# LDO_Regulator.net
KiCad netlist of a schematic drawn in Altium Designer
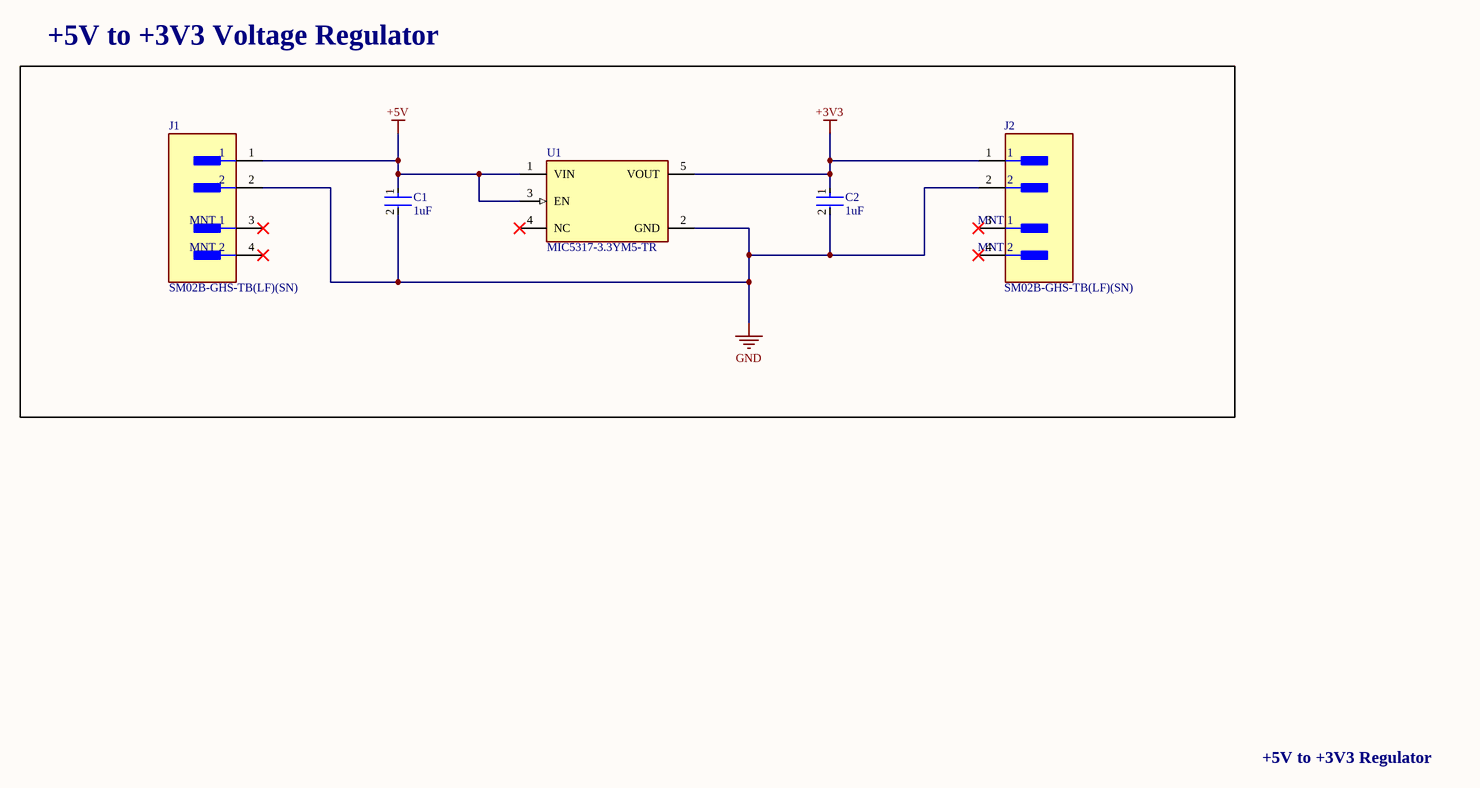
[diagram p0: LDO Regulator.SchDoc]

(export (version "E")
  (design (tool "Eeschema 10.0.6"))
  (components
    (comp (ref "C1")
      (value "1uF")
      (footprint "FP-CC0805-0_85-MFG")
      (description "CAP CER 1UF 10V X7R 0805")
      (fields
        (field (name "MANUFACTURER") "Yageo")
        (field (name "OCTOPART") "https://octopart.com/cc0805kkx7r6bb105-yageo-42522859")
      )
      (libsource (lib "Altium Content Vault") (part "11868f565c42a9108669ba33697ecf6"))
    )
    (comp (ref "C2")
      (value "1uF")
      (footprint "FP-CC0805-0_85-MFG")
      (description "CAP CER 1UF 10V X7R 0805")
      (fields
        (field (name "MANUFACTURER") "Yageo")
        (field (name "OCTOPART") "https://octopart.com/cc0805kkx7r6bb105-yageo-42522859")
      )
      (libsource (lib "Altium Content Vault") (part "11868f565c42a9108669ba33697ecf6"))
    )
    (comp (ref "J1")
      (value "SM02B-GHS-TB(LF)(SN)")
      (footprint "FP-SM02B-GHS-TB_LF_SN-MFG")
      (description "CONN HEADER SMD R/A 2POS 1.25MM")
      (libsource (lib "Altium Content Vault") (part "56ec3178a87b3978bdc1b3682cd516a"))
    )
    (comp (ref "J2")
      (value "SM02B-GHS-TB(LF)(SN)")
      (footprint "FP-SM02B-GHS-TB_LF_SN-MFG")
      (description "CONN HEADER SMD R/A 2POS 1.25MM")
      (libsource (lib "") (part "56ec3178a87b3978bdc1b3682cd516a_1"))
    )
    (comp (ref "U1")
      (value "MIC5317-3.3YM5-TR")
      (footprint "FP-SOT23-5LD-PL-1-MFG")
      (description "IC REG LINEAR 3.3V 150MA SOT23-5")
      (libsource (lib "Altium Content Vault") (part "0a093dae7315cdc977fd108dde87457"))
    )
  )
  (nets
    (net (code "1") (name "+3V3") (class "Default")
      (node (ref "C2") (pin "1") (pinfunction "1_1") (pintype "passive"))
      (node (ref "J2") (pin "1") (pinfunction "1_1") (pintype "passive"))
      (node (ref "U1") (pin "5") (pinfunction "VOUT_5") (pintype "power_in"))
    )
    (net (code "2") (name "+5V") (class "Default")
      (node (ref "C1") (pin "1") (pinfunction "1_1") (pintype "passive"))
      (node (ref "J1") (pin "1") (pinfunction "1_1") (pintype "passive"))
      (node (ref "U1") (pin "1") (pinfunction "VIN_1") (pintype "power_in"))
      (node (ref "U1") (pin "3") (pinfunction "EN_3") (pintype "input"))
    )
    (net (code "3") (name "GND") (class "Default")
      (node (ref "C1") (pin "2") (pinfunction "2_2") (pintype "passive"))
      (node (ref "C2") (pin "2") (pinfunction "2_2") (pintype "passive"))
      (node (ref "J1") (pin "2") (pinfunction "2_2") (pintype "passive"))
      (node (ref "J2") (pin "2") (pinfunction "2_2") (pintype "passive"))
      (node (ref "U1") (pin "2") (pinfunction "GND_2") (pintype "power_in"))
    )
    (net (code "4") (name "unconnected-(J1-MNT_1-Pad3)") (class "Default")
      (node (ref "J1") (pin "3") (pinfunction "MNT_1_3") (pintype "passive+no_connect"))
    )
    (net (code "5") (name "unconnected-(J1-MNT_2-Pad4)") (class "Default")
      (node (ref "J1") (pin "4") (pinfunction "MNT_2_4") (pintype "passive+no_connect"))
    )
    (net (code "6") (name "unconnected-(J2-MNT_1-Pad3)") (class "Default")
      (node (ref "J2") (pin "3") (pinfunction "MNT_1_3") (pintype "passive+no_connect"))
    )
    (net (code "7") (name "unconnected-(J2-MNT_2-Pad4)") (class "Default")
      (node (ref "J2") (pin "4") (pinfunction "MNT_2_4") (pintype "passive+no_connect"))
    )
    (net (code "8") (name "unconnected-(U1-NC-Pad4)") (class "Default")
      (node (ref "U1") (pin "4") (pinfunction "NC_4") (pintype "passive+no_connect"))
    )
  )
)
